# Launch-28020_V2_routed.net
KiCad netlist of a schematic drawn in EAGLE
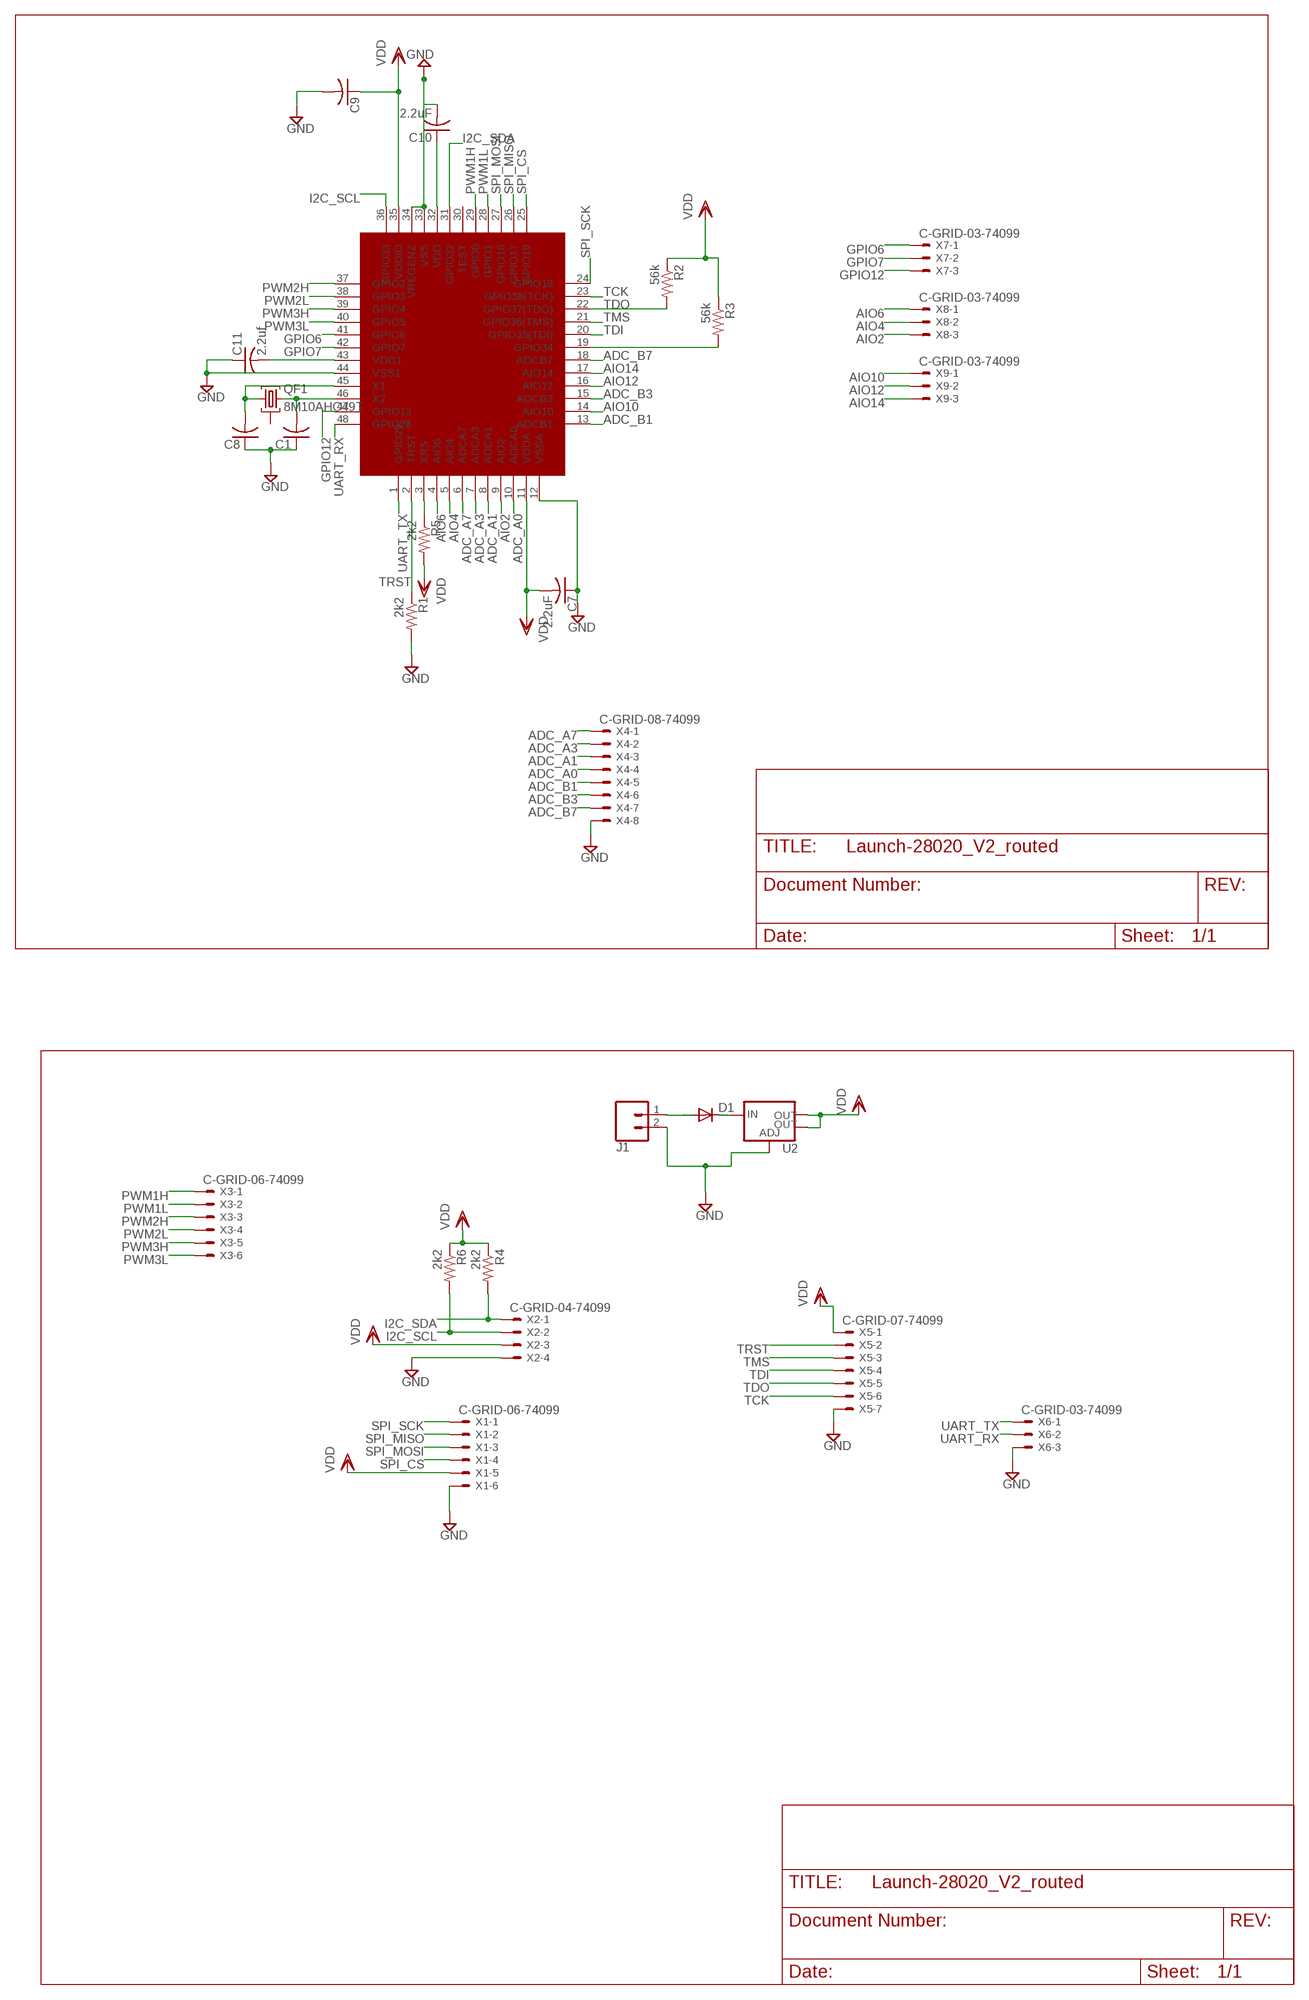
[diagram p0: schematic, sheet 1]

(export (version "E")
  (design (tool "Eeschema 10.0.6"))
  (components
    (comp (ref "C1")
      (value "C-USC1206")
      (footprint "eagle-import:C1206")
      (libsource (lib "eagle-import") (part "C-USC1206"))
    )
    (comp (ref "C7")
      (value "2.2uF")
      (footprint "eagle-import:C1206")
      (libsource (lib "eagle-import") (part "C-USC1206"))
    )
    (comp (ref "C8")
      (value "C-USC1206")
      (footprint "eagle-import:C1206")
      (libsource (lib "eagle-import") (part "C-USC1206"))
    )
    (comp (ref "C9")
      (value "C-USC1206")
      (footprint "eagle-import:C1206")
      (libsource (lib "eagle-import") (part "C-USC1206"))
    )
    (comp (ref "C10")
      (value "2.2uF")
      (footprint "eagle-import:C1206")
      (libsource (lib "eagle-import") (part "C-USC1206"))
    )
    (comp (ref "C11")
      (value "2.2uf")
      (footprint "eagle-import:C1206")
      (libsource (lib "eagle-import") (part "C-USC1206"))
    )
    (comp (ref "D1")
      (value "DIODE-SOD106-W")
      (footprint "eagle-import:SOD106-W")
      (libsource (lib "eagle-import") (part "DIODE-SOD106-W"))
    )
    (comp (ref "J1")
      (value "CONN_023.5MM-NO_SILK")
      (footprint "eagle-import:SCREWTERMINAL-3.5MM-2-NS")
      (libsource (lib "eagle-import") (part "CONN_023.5MM-NO_SILK"))
    )
    (comp (ref "QF1")
      (value "8M10AHC49T")
      (footprint "eagle-import:HC49U")
      (libsource (lib "eagle-import") (part "8M10AHC49T"))
    )
    (comp (ref "R1")
      (value "2k2")
      (footprint "eagle-import:M1206")
      (libsource (lib "eagle-import") (part "R-US_M1206"))
    )
    (comp (ref "R2")
      (value "56k")
      (footprint "eagle-import:M1206")
      (libsource (lib "eagle-import") (part "R-US_M1206"))
    )
    (comp (ref "R3")
      (value "56k")
      (footprint "eagle-import:M1206")
      (libsource (lib "eagle-import") (part "R-US_M1206"))
    )
    (comp (ref "R4")
      (value "2k2")
      (footprint "eagle-import:M1206")
      (libsource (lib "eagle-import") (part "R-US_M1206"))
    )
    (comp (ref "R5")
      (value "2k2")
      (footprint "eagle-import:M1206")
      (libsource (lib "eagle-import") (part "R-US_M1206"))
    )
    (comp (ref "R6")
      (value "2k2")
      (footprint "eagle-import:M1206")
      (libsource (lib "eagle-import") (part "R-US_M1206"))
    )
    (comp (ref "U$1")
      (value "TMS320F28020")
      (footprint "eagle-import:LQFP-48")
      (libsource (lib "eagle-import") (part "TMS320F28020"))
    )
    (comp (ref "U2")
      (value "V_REG_LM1117SOT223")
      (footprint "eagle-import:SOT223")
      (libsource (lib "eagle-import") (part "V_REG_LM1117SOT223"))
    )
    (comp (ref "X1")
      (value "C-GRID-06-74099")
      (footprint "eagle-import:74099-06")
      (libsource (lib "eagle-import") (part "C-GRID-06-74099"))
    )
    (comp (ref "X2")
      (value "C-GRID-04-74099")
      (footprint "eagle-import:74099-04")
      (libsource (lib "eagle-import") (part "C-GRID-04-74099"))
    )
    (comp (ref "X3")
      (value "C-GRID-06-74099")
      (footprint "eagle-import:74099-06")
      (libsource (lib "eagle-import") (part "C-GRID-06-74099"))
    )
    (comp (ref "X4")
      (value "C-GRID-08-74099")
      (footprint "eagle-import:74099-08")
      (libsource (lib "eagle-import") (part "C-GRID-08-74099"))
    )
    (comp (ref "X5")
      (value "C-GRID-07-74099")
      (footprint "eagle-import:74099-07")
      (libsource (lib "eagle-import") (part "C-GRID-07-74099"))
    )
    (comp (ref "X6")
      (value "C-GRID-03-74099")
      (footprint "eagle-import:74099-03")
      (libsource (lib "eagle-import") (part "C-GRID-03-74099"))
    )
    (comp (ref "X7")
      (value "C-GRID-03-74099")
      (footprint "eagle-import:74099-03")
      (libsource (lib "eagle-import") (part "C-GRID-03-74099"))
    )
    (comp (ref "X8")
      (value "C-GRID-03-74099")
      (footprint "eagle-import:74099-03")
      (libsource (lib "eagle-import") (part "C-GRID-03-74099"))
    )
    (comp (ref "X9")
      (value "C-GRID-03-74099")
      (footprint "eagle-import:74099-03")
      (libsource (lib "eagle-import") (part "C-GRID-03-74099"))
    )
  )
  (nets
    (net (code "1") (name "/ADC_A0") (class "Default")
      (node (ref "U$1") (pin "10") (pinfunction "ADCA0_10") (pintype "bidirectional"))
      (node (ref "X4") (pin "4") (pinfunction "S_4") (pintype "passive"))
    )
    (net (code "2") (name "/ADC_A1") (class "Default")
      (node (ref "U$1") (pin "8") (pinfunction "ADCA1_8") (pintype "bidirectional"))
      (node (ref "X4") (pin "3") (pinfunction "S_3") (pintype "passive"))
    )
    (net (code "3") (name "/ADC_A3") (class "Default")
      (node (ref "U$1") (pin "7") (pinfunction "ADCA3_7") (pintype "bidirectional"))
      (node (ref "X4") (pin "2") (pinfunction "S_2") (pintype "passive"))
    )
    (net (code "4") (name "/ADC_A7") (class "Default")
      (node (ref "U$1") (pin "6") (pinfunction "ADCA7_6") (pintype "bidirectional"))
      (node (ref "X4") (pin "1") (pinfunction "S_1") (pintype "passive"))
    )
    (net (code "5") (name "/ADC_B1") (class "Default")
      (node (ref "U$1") (pin "13") (pinfunction "ADCB1_13") (pintype "bidirectional"))
      (node (ref "X4") (pin "5") (pinfunction "S_5") (pintype "passive"))
    )
    (net (code "6") (name "/ADC_B3") (class "Default")
      (node (ref "U$1") (pin "15") (pinfunction "ADCB3_15") (pintype "bidirectional"))
      (node (ref "X4") (pin "6") (pinfunction "S_6") (pintype "passive"))
    )
    (net (code "7") (name "/ADC_B7") (class "Default")
      (node (ref "U$1") (pin "18") (pinfunction "ADCB7_18") (pintype "bidirectional"))
      (node (ref "X4") (pin "7") (pinfunction "S_7") (pintype "passive"))
    )
    (net (code "8") (name "/AIO2") (class "Default")
      (node (ref "U$1") (pin "9") (pinfunction "AIO2_9") (pintype "bidirectional"))
      (node (ref "X8") (pin "3") (pinfunction "S_3") (pintype "passive"))
    )
    (net (code "9") (name "/AIO4") (class "Default")
      (node (ref "U$1") (pin "5") (pinfunction "AIO4_5") (pintype "bidirectional"))
      (node (ref "X8") (pin "2") (pinfunction "S_2") (pintype "passive"))
    )
    (net (code "10") (name "/AIO6") (class "Default")
      (node (ref "U$1") (pin "4") (pinfunction "AIO6_4") (pintype "bidirectional"))
      (node (ref "X8") (pin "1") (pinfunction "S_1") (pintype "passive"))
    )
    (net (code "11") (name "/AIO10") (class "Default")
      (node (ref "U$1") (pin "14") (pinfunction "AIO10_14") (pintype "bidirectional"))
      (node (ref "X9") (pin "1") (pinfunction "S_1") (pintype "passive"))
    )
    (net (code "12") (name "/AIO12") (class "Default")
      (node (ref "U$1") (pin "16") (pinfunction "AIO12_16") (pintype "bidirectional"))
      (node (ref "X9") (pin "2") (pinfunction "S_2") (pintype "passive"))
    )
    (net (code "13") (name "/AIO14") (class "Default")
      (node (ref "U$1") (pin "17") (pinfunction "AIO14_17") (pintype "bidirectional"))
      (node (ref "X9") (pin "3") (pinfunction "S_3") (pintype "passive"))
    )
    (net (code "14") (name "/GPIO6") (class "Default")
      (node (ref "U$1") (pin "41") (pinfunction "GPIO6_41") (pintype "bidirectional"))
      (node (ref "X7") (pin "1") (pinfunction "S_1") (pintype "passive"))
    )
    (net (code "15") (name "/GPIO7") (class "Default")
      (node (ref "U$1") (pin "42") (pinfunction "GPIO7_42") (pintype "bidirectional"))
      (node (ref "X7") (pin "2") (pinfunction "S_2") (pintype "passive"))
    )
    (net (code "16") (name "/GPIO12") (class "Default")
      (node (ref "U$1") (pin "47") (pinfunction "GPIO12_47") (pintype "bidirectional"))
      (node (ref "X7") (pin "3") (pinfunction "S_3") (pintype "passive"))
    )
    (net (code "17") (name "/I2C_SCL") (class "Default")
      (node (ref "R6") (pin "2") (pinfunction "2_2") (pintype "passive"))
      (node (ref "U$1") (pin "36") (pinfunction "GPIO33_36") (pintype "bidirectional"))
      (node (ref "X2") (pin "2") (pinfunction "S_2") (pintype "passive"))
    )
    (net (code "18") (name "/I2C_SDA") (class "Default")
      (node (ref "R4") (pin "2") (pinfunction "2_2") (pintype "passive"))
      (node (ref "U$1") (pin "31") (pinfunction "GPIO32_31") (pintype "bidirectional"))
      (node (ref "X2") (pin "1") (pinfunction "S_1") (pintype "passive"))
    )
    (net (code "19") (name "/PWM1H") (class "Default")
      (node (ref "U$1") (pin "29") (pinfunction "GPIO0_29") (pintype "bidirectional"))
      (node (ref "X3") (pin "1") (pinfunction "S_1") (pintype "passive"))
    )
    (net (code "20") (name "/PWM1L") (class "Default")
      (node (ref "U$1") (pin "28") (pinfunction "GPIO1_28") (pintype "bidirectional"))
      (node (ref "X3") (pin "2") (pinfunction "S_2") (pintype "passive"))
    )
    (net (code "21") (name "/PWM2H") (class "Default")
      (node (ref "U$1") (pin "37") (pinfunction "GPIO2_37") (pintype "bidirectional"))
      (node (ref "X3") (pin "3") (pinfunction "S_3") (pintype "passive"))
    )
    (net (code "22") (name "/PWM2L") (class "Default")
      (node (ref "U$1") (pin "38") (pinfunction "GPIO3_38") (pintype "bidirectional"))
      (node (ref "X3") (pin "4") (pinfunction "S_4") (pintype "passive"))
    )
    (net (code "23") (name "/PWM3H") (class "Default")
      (node (ref "U$1") (pin "39") (pinfunction "GPIO4_39") (pintype "bidirectional"))
      (node (ref "X3") (pin "5") (pinfunction "S_5") (pintype "passive"))
    )
    (net (code "24") (name "/PWM3L") (class "Default")
      (node (ref "U$1") (pin "40") (pinfunction "GPIO5_40") (pintype "bidirectional"))
      (node (ref "X3") (pin "6") (pinfunction "S_6") (pintype "passive"))
    )
    (net (code "25") (name "/SPI_CS") (class "Default")
      (node (ref "U$1") (pin "25") (pinfunction "GPIO19_25") (pintype "bidirectional"))
      (node (ref "X1") (pin "4") (pinfunction "S_4") (pintype "passive"))
    )
    (net (code "26") (name "/SPI_MISO") (class "Default")
      (node (ref "U$1") (pin "26") (pinfunction "GPIO17_26") (pintype "bidirectional"))
      (node (ref "X1") (pin "2") (pinfunction "S_2") (pintype "passive"))
    )
    (net (code "27") (name "/SPI_MOSI") (class "Default")
      (node (ref "U$1") (pin "27") (pinfunction "GPIO16_27") (pintype "bidirectional"))
      (node (ref "X1") (pin "3") (pinfunction "S_3") (pintype "passive"))
    )
    (net (code "28") (name "/SPI_SCK") (class "Default")
      (node (ref "U$1") (pin "24") (pinfunction "GPIO18_24") (pintype "bidirectional"))
      (node (ref "X1") (pin "1") (pinfunction "S_1") (pintype "passive"))
    )
    (net (code "29") (name "/TCK") (class "Default")
      (node (ref "U$1") (pin "23") (pinfunction "GPIO38(TCK)_23") (pintype "bidirectional"))
      (node (ref "X5") (pin "6") (pinfunction "S_6") (pintype "passive"))
    )
    (net (code "30") (name "/TDI") (class "Default")
      (node (ref "U$1") (pin "20") (pinfunction "GPIO35(TDI)_20") (pintype "bidirectional"))
      (node (ref "X5") (pin "4") (pinfunction "S_4") (pintype "passive"))
    )
    (net (code "31") (name "/TDO") (class "Default")
      (node (ref "R2") (pin "2") (pinfunction "2_2") (pintype "passive"))
      (node (ref "U$1") (pin "22") (pinfunction "GPIO37(TDO)_22") (pintype "bidirectional"))
      (node (ref "X5") (pin "5") (pinfunction "S_5") (pintype "passive"))
    )
    (net (code "32") (name "/TMS") (class "Default")
      (node (ref "U$1") (pin "21") (pinfunction "GPIO36(TMS)_21") (pintype "bidirectional"))
      (node (ref "X5") (pin "3") (pinfunction "S_3") (pintype "passive"))
    )
    (net (code "33") (name "/TRST") (class "Default")
      (node (ref "R1") (pin "1") (pinfunction "1_1") (pintype "passive"))
      (node (ref "U$1") (pin "2") (pinfunction "TRST_2") (pintype "bidirectional"))
      (node (ref "X5") (pin "2") (pinfunction "S_2") (pintype "passive"))
    )
    (net (code "34") (name "/UART_RX") (class "Default")
      (node (ref "U$1") (pin "48") (pinfunction "GPIO28_48") (pintype "bidirectional"))
      (node (ref "X6") (pin "2") (pinfunction "S_2") (pintype "passive"))
    )
    (net (code "35") (name "/UART_TX") (class "Default")
      (node (ref "U$1") (pin "1") (pinfunction "GPIO29_1") (pintype "bidirectional"))
      (node (ref "X6") (pin "1") (pinfunction "S_1") (pintype "passive"))
    )
    (net (code "36") (name "GND") (class "Default")
      (node (ref "C1") (pin "1") (pinfunction "1_1") (pintype "passive"))
      (node (ref "C10") (pin "2") (pinfunction "2_2") (pintype "passive"))
      (node (ref "C11") (pin "1") (pinfunction "1_1") (pintype "passive"))
      (node (ref "C7") (pin "1") (pinfunction "1_1") (pintype "passive"))
      (node (ref "C8") (pin "1") (pinfunction "1_1") (pintype "passive"))
      (node (ref "C9") (pin "2") (pinfunction "2_2") (pintype "passive"))
      (node (ref "J1") (pin "2") (pinfunction "2_2") (pintype "passive"))
      (node (ref "R1") (pin "2") (pinfunction "2_2") (pintype "passive"))
      (node (ref "U$1") (pin "12") (pinfunction "VSSA_12") (pintype "bidirectional"))
      (node (ref "U$1") (pin "33") (pinfunction "VSS_33") (pintype "bidirectional"))
      (node (ref "U$1") (pin "34") (pinfunction "VREGENZ_34") (pintype "bidirectional"))
      (node (ref "U$1") (pin "44") (pinfunction "VSS1_44") (pintype "bidirectional"))
      (node (ref "U2") (pin "1") (pinfunction "ADJ_1") (pintype "input"))
      (node (ref "X1") (pin "6") (pinfunction "S_6") (pintype "passive"))
      (node (ref "X2") (pin "4") (pinfunction "S_4") (pintype "passive"))
      (node (ref "X4") (pin "8") (pinfunction "S_8") (pintype "passive"))
      (node (ref "X5") (pin "7") (pinfunction "S_7") (pintype "passive"))
      (node (ref "X6") (pin "3") (pinfunction "S_3") (pintype "passive"))
    )
    (net (code "37") (name "Net-(D1-PadA)") (class "Default")
      (node (ref "D1") (pin "A") (pinfunction "A_A") (pintype "passive"))
      (node (ref "J1") (pin "1") (pinfunction "1_1") (pintype "passive"))
    )
    (net (code "38") (name "Net-(U$1-GPIO34)") (class "Default")
      (node (ref "R3") (pin "2") (pinfunction "2_2") (pintype "passive"))
      (node (ref "U$1") (pin "19") (pinfunction "GPIO34_19") (pintype "bidirectional"))
    )
    (net (code "39") (name "Net-(U$1-VDD)") (class "Default")
      (node (ref "C10") (pin "1") (pinfunction "1_1") (pintype "passive"))
      (node (ref "U$1") (pin "32") (pinfunction "VDD_32") (pintype "bidirectional"))
    )
    (net (code "40") (name "Net-(U$1-VDD1)") (class "Default")
      (node (ref "C11") (pin "2") (pinfunction "2_2") (pintype "passive"))
      (node (ref "U$1") (pin "43") (pinfunction "VDD1_43") (pintype "bidirectional"))
    )
    (net (code "41") (name "Net-(U$1-X1)") (class "Default")
      (node (ref "C8") (pin "2") (pinfunction "2_2") (pintype "passive"))
      (node (ref "QF1") (pin "1") (pinfunction "1_1") (pintype "passive"))
      (node (ref "U$1") (pin "45") (pinfunction "X1_45") (pintype "bidirectional"))
    )
    (net (code "42") (name "Net-(U$1-X2)") (class "Default")
      (node (ref "C1") (pin "2") (pinfunction "2_2") (pintype "passive"))
      (node (ref "QF1") (pin "3") (pinfunction "3_3") (pintype "passive"))
      (node (ref "U$1") (pin "46") (pinfunction "X2_46") (pintype "bidirectional"))
    )
    (net (code "43") (name "Net-(U$1-XRS)") (class "Default")
      (node (ref "R5") (pin "1") (pinfunction "1_1") (pintype "passive"))
      (node (ref "U$1") (pin "3") (pinfunction "XRS_3") (pintype "bidirectional"))
    )
    (net (code "44") (name "Net-(U2-IN)") (class "Default")
      (node (ref "D1") (pin "C") (pinfunction "C_C") (pintype "passive"))
      (node (ref "U2") (pin "3") (pinfunction "IN_3") (pintype "input"))
    )
    (net (code "45") (name "VDD") (class "Default")
      (node (ref "C7") (pin "2") (pinfunction "2_2") (pintype "passive"))
      (node (ref "C9") (pin "1") (pinfunction "1_1") (pintype "passive"))
      (node (ref "R2") (pin "1") (pinfunction "1_1") (pintype "passive"))
      (node (ref "R3") (pin "1") (pinfunction "1_1") (pintype "passive"))
      (node (ref "R4") (pin "1") (pinfunction "1_1") (pintype "passive"))
      (node (ref "R5") (pin "2") (pinfunction "2_2") (pintype "passive"))
      (node (ref "R6") (pin "1") (pinfunction "1_1") (pintype "passive"))
      (node (ref "U$1") (pin "11") (pinfunction "VDDA_11") (pintype "bidirectional"))
      (node (ref "U$1") (pin "35") (pinfunction "VDDIO_35") (pintype "bidirectional"))
      (node (ref "U2") (pin "2") (pinfunction "OUT_2") (pintype "output"))
      (node (ref "U2") (pin "4") (pinfunction "OUT_4") (pintype "output"))
      (node (ref "X1") (pin "5") (pinfunction "S_5") (pintype "passive"))
      (node (ref "X2") (pin "3") (pinfunction "S_3") (pintype "passive"))
      (node (ref "X5") (pin "1") (pinfunction "S_1") (pintype "passive"))
    )
    (net (code "46") (name "unconnected-(QF1-Pad2)") (class "Default")
      (node (ref "QF1") (pin "2") (pinfunction "2_2") (pintype "passive"))
    )
    (net (code "47") (name "unconnected-(U$1-TEST-Pad30)") (class "Default")
      (node (ref "U$1") (pin "30") (pinfunction "TEST_30") (pintype "bidirectional"))
    )
  )
)
